# SmartBell_v1_0.net
KiCad netlist of a schematic drawn in EAGLE
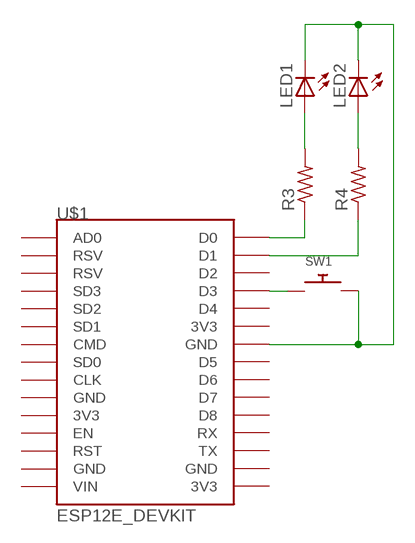
[diagram p0: schematic, sheet 1]

(export (version "E")
  (design (tool "Eeschema 10.0.6"))
  (components
    (comp (ref "LED1")
      (value "LED5MM")
      (footprint "eagle-import:LED5MM")
      (libsource (lib "eagle-import") (part "LED5MM"))
    )
    (comp (ref "LED2")
      (value "LED5MM")
      (footprint "eagle-import:LED5MM")
      (libsource (lib "eagle-import") (part "LED5MM"))
    )
    (comp (ref "R3")
      (value "R-US_0207/10")
      (footprint "eagle-import:0207_10")
      (libsource (lib "eagle-import") (part "R-US_0207/10"))
    )
    (comp (ref "R4")
      (value "R-US_0207/10")
      (footprint "eagle-import:0207_10")
      (libsource (lib "eagle-import") (part "R-US_0207/10"))
    )
    (comp (ref "SW1")
      (value "SWITCH_PUSHBUTTONSOFTTOUCHSMD_SJ")
      (footprint "eagle-import:PUSHBUTTON_SMD_SJ")
      (libsource (lib "eagle-import") (part "SWITCH_PUSHBUTTONSOFTTOUCHSMD_SJ"))
    )
    (comp (ref "U$1")
      (value "ESP12E_DEVKIT")
      (footprint "eagle-import:ESP12E_DEVKIT")
      (libsource (lib "eagle-import") (part "ESP12E_DEVKIT"))
    )
  )
  (nets
    (net (code "1") (name "Net-(LED1-C)") (class "Default")
      (node (ref "LED1") (pin "K") (pinfunction "C_K") (pintype "passive"))
      (node (ref "LED2") (pin "K") (pinfunction "C_K") (pintype "passive"))
      (node (ref "SW1") (pin "P$2") (pinfunction "P$2_P$2") (pintype "passive"))
      (node (ref "U$1") (pin "GND@2") (pinfunction "GND_GND@2") (pintype "bidirectional"))
    )
    (net (code "2") (name "Net-(LED1-PadA)") (class "Default")
      (node (ref "LED1") (pin "A") (pinfunction "A_A") (pintype "passive"))
      (node (ref "R3") (pin "2") (pinfunction "2_2") (pintype "passive"))
    )
    (net (code "3") (name "Net-(LED2-PadA)") (class "Default")
      (node (ref "LED2") (pin "A") (pinfunction "A_A") (pintype "passive"))
      (node (ref "R4") (pin "2") (pinfunction "2_2") (pintype "passive"))
    )
    (net (code "4") (name "Net-(R3-Pad1)") (class "Default")
      (node (ref "R3") (pin "1") (pinfunction "1_1") (pintype "passive"))
      (node (ref "U$1") (pin "D0") (pinfunction "D0_D0") (pintype "bidirectional"))
    )
    (net (code "5") (name "Net-(R4-Pad1)") (class "Default")
      (node (ref "R4") (pin "1") (pinfunction "1_1") (pintype "passive"))
      (node (ref "U$1") (pin "D1") (pinfunction "D1_D1") (pintype "bidirectional"))
    )
    (net (code "6") (name "Net-(SW1-PadP$1)") (class "Default")
      (node (ref "SW1") (pin "P$1") (pinfunction "P$1_P$1") (pintype "passive"))
      (node (ref "U$1") (pin "D3") (pinfunction "D3_D3") (pintype "bidirectional"))
    )
    (net (code "7") (name "unconnected-(U$1-3V3-Pad3V3@0)") (class "Default")
      (node (ref "U$1") (pin "3V3@0") (pinfunction "3V3_3V3@0") (pintype "bidirectional"))
    )
    (net (code "8") (name "unconnected-(U$1-3V3-Pad3V3@1)") (class "Default")
      (node (ref "U$1") (pin "3V3@1") (pinfunction "3V3_3V3@1") (pintype "bidirectional"))
    )
    (net (code "9") (name "unconnected-(U$1-3V3-Pad3V3@2)") (class "Default")
      (node (ref "U$1") (pin "3V3@2") (pinfunction "3V3_3V3@2") (pintype "bidirectional"))
    )
    (net (code "10") (name "unconnected-(U$1-GND-PadGND@0)") (class "Default")
      (node (ref "U$1") (pin "GND@0") (pinfunction "GND_GND@0") (pintype "bidirectional"))
    )
    (net (code "11") (name "unconnected-(U$1-GND-PadGND@1)") (class "Default")
      (node (ref "U$1") (pin "GND@1") (pinfunction "GND_GND@1") (pintype "bidirectional"))
    )
    (net (code "12") (name "unconnected-(U$1-GND-PadGND@3)") (class "Default")
      (node (ref "U$1") (pin "GND@3") (pinfunction "GND_GND@3") (pintype "bidirectional"))
    )
    (net (code "13") (name "unconnected-(U$1-PadAD0)") (class "Default")
      (node (ref "U$1") (pin "AD0") (pinfunction "AD0_AD0") (pintype "bidirectional"))
    )
    (net (code "14") (name "unconnected-(U$1-PadCLK)") (class "Default")
      (node (ref "U$1") (pin "CLK") (pinfunction "CLK_CLK") (pintype "bidirectional"))
    )
    (net (code "15") (name "unconnected-(U$1-PadCMD)") (class "Default")
      (node (ref "U$1") (pin "CMD") (pinfunction "CMD_CMD") (pintype "bidirectional"))
    )
    (net (code "16") (name "unconnected-(U$1-PadD2)") (class "Default")
      (node (ref "U$1") (pin "D2") (pinfunction "D2_D2") (pintype "bidirectional"))
    )
    (net (code "17") (name "unconnected-(U$1-PadD4)") (class "Default")
      (node (ref "U$1") (pin "D4") (pinfunction "D4_D4") (pintype "bidirectional"))
    )
    (net (code "18") (name "unconnected-(U$1-PadD5)") (class "Default")
      (node (ref "U$1") (pin "D5") (pinfunction "D5_D5") (pintype "bidirectional"))
    )
    (net (code "19") (name "unconnected-(U$1-PadD6)") (class "Default")
      (node (ref "U$1") (pin "D6") (pinfunction "D6_D6") (pintype "bidirectional"))
    )
    (net (code "20") (name "unconnected-(U$1-PadD7)") (class "Default")
      (node (ref "U$1") (pin "D7") (pinfunction "D7_D7") (pintype "bidirectional"))
    )
    (net (code "21") (name "unconnected-(U$1-PadD8)") (class "Default")
      (node (ref "U$1") (pin "D8") (pinfunction "D8_D8") (pintype "bidirectional"))
    )
    (net (code "22") (name "unconnected-(U$1-PadEN)") (class "Default")
      (node (ref "U$1") (pin "EN") (pinfunction "EN_EN") (pintype "bidirectional"))
    )
    (net (code "23") (name "unconnected-(U$1-PadRST)") (class "Default")
      (node (ref "U$1") (pin "RST") (pinfunction "RST_RST") (pintype "bidirectional"))
    )
    (net (code "24") (name "unconnected-(U$1-PadRX)") (class "Default")
      (node (ref "U$1") (pin "RX") (pinfunction "RX_RX") (pintype "bidirectional"))
    )
    (net (code "25") (name "unconnected-(U$1-PadSD0)") (class "Default")
      (node (ref "U$1") (pin "SD0") (pinfunction "SD0_SD0") (pintype "bidirectional"))
    )
    (net (code "26") (name "unconnected-(U$1-PadSD1)") (class "Default")
      (node (ref "U$1") (pin "SD1") (pinfunction "SD1_SD1") (pintype "bidirectional"))
    )
    (net (code "27") (name "unconnected-(U$1-PadSD2)") (class "Default")
      (node (ref "U$1") (pin "SD2") (pinfunction "SD2_SD2") (pintype "bidirectional"))
    )
    (net (code "28") (name "unconnected-(U$1-PadSD3)") (class "Default")
      (node (ref "U$1") (pin "SD3") (pinfunction "SD3_SD3") (pintype "bidirectional"))
    )
    (net (code "29") (name "unconnected-(U$1-PadTX)") (class "Default")
      (node (ref "U$1") (pin "TX") (pinfunction "TX_TX") (pintype "bidirectional"))
    )
    (net (code "30") (name "unconnected-(U$1-PadVIN)") (class "Default")
      (node (ref "U$1") (pin "VIN") (pinfunction "VIN_VIN") (pintype "bidirectional"))
    )
    (net (code "31") (name "unconnected-(U$1-RSV-PadRSV@0)") (class "Default")
      (node (ref "U$1") (pin "RSV@0") (pinfunction "RSV_RSV@0") (pintype "bidirectional"))
    )
    (net (code "32") (name "unconnected-(U$1-RSV-PadRSV@1)") (class "Default")
      (node (ref "U$1") (pin "RSV@1") (pinfunction "RSV_RSV@1") (pintype "bidirectional"))
    )
  )
)
